# Safety_Devices.net
KiCad netlist of a schematic drawn in Altium Designer
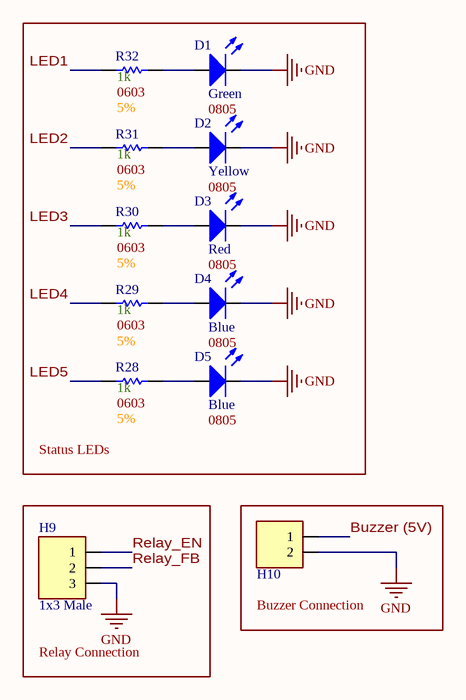
[diagram p0: Safety Devices.SchDoc]

(export (version "E")
  (design (tool "Eeschema 10.0.6"))
  (components
    (comp (ref "D1")
      (value "SMD LED")
      (footprint "[LED] SMD 0805")
      (description "Generic")
      (fields (field (name "COLOR") "Green") (field (name "SIZE PACKAGE") "0805"))
      (libsource (lib "RADM Components") (part "[LED] SMD"))
    )
    (comp (ref "D2")
      (value "SMD LED")
      (footprint "[LED] SMD 0805")
      (description "Generic")
      (fields (field (name "COLOR") "Yellow") (field (name "SIZE PACKAGE") "0805"))
      (libsource (lib "RADM Components") (part "[LED] SMD"))
    )
    (comp (ref "D3")
      (value "SMD LED")
      (footprint "[LED] SMD 0805")
      (description "Generic")
      (fields (field (name "COLOR") "Red") (field (name "SIZE PACKAGE") "0805"))
      (libsource (lib "RADM Components") (part "[LED] SMD"))
    )
    (comp (ref "D4")
      (value "SMD LED")
      (footprint "[LED] SMD 0805")
      (description "Generic")
      (fields (field (name "COLOR") "Blue") (field (name "SIZE PACKAGE") "0805"))
      (libsource (lib "RADM Components") (part "[LED] SMD"))
    )
    (comp (ref "D5")
      (value "SMD LED")
      (footprint "[LED] SMD 0805")
      (description "Generic")
      (fields (field (name "COLOR") "Blue") (field (name "SIZE PACKAGE") "0805"))
      (libsource (lib "RADM Components") (part "[LED] SMD"))
    )
    (comp (ref "H9")
      (value "1x3 Male")
      (footprint "[Header] Shrouded 1x3 Male")
      (description "070543-0037\r\nMates with 005057-9403")
      (libsource (lib "RADM Connectors") (part "[Header] Shrouded 1x3 Male"))
    )
    (comp (ref "H10")
      (value "1x2 Male")
      (footprint "[Header] Shrouded 1x2 Male")
      (description "0705430036\r\nMates with 0050579402")
      (libsource (lib "RADM Connectors") (part "[Header] Shrouded 1x2 Male"))
    )
    (comp (ref "R28")
      (value "[Res] SMD Resistor")
      (footprint "[Res] SMD 0603")
      (description "Generic")
      (fields
        (field (name "RESISTANCE") "1k")
        (field (name "SIZE PACKAGE") "0603")
        (field (name "TOLERANCE") "5%")
      )
      (libsource (lib "RADM Components") (part "[Res] SMD Resistor"))
    )
    (comp (ref "R29")
      (value "[Res] SMD Resistor")
      (footprint "[Res] SMD 0603")
      (description "Generic")
      (fields
        (field (name "RESISTANCE") "1k")
        (field (name "SIZE PACKAGE") "0603")
        (field (name "TOLERANCE") "5%")
      )
      (libsource (lib "RADM Components") (part "[Res] SMD Resistor"))
    )
    (comp (ref "R30")
      (value "[Res] SMD Resistor")
      (footprint "[Res] SMD 0603")
      (description "Generic")
      (fields
        (field (name "RESISTANCE") "1k")
        (field (name "SIZE PACKAGE") "0603")
        (field (name "TOLERANCE") "5%")
      )
      (libsource (lib "RADM Components") (part "[Res] SMD Resistor"))
    )
    (comp (ref "R31")
      (value "[Res] SMD Resistor")
      (footprint "[Res] SMD 0603")
      (description "Generic")
      (fields
        (field (name "RESISTANCE") "1k")
        (field (name "SIZE PACKAGE") "0603")
        (field (name "TOLERANCE") "5%")
      )
      (libsource (lib "RADM Components") (part "[Res] SMD Resistor"))
    )
    (comp (ref "R32")
      (value "[Res] SMD Resistor")
      (footprint "[Res] SMD 0603")
      (description "Generic")
      (fields
        (field (name "RESISTANCE") "1k")
        (field (name "SIZE PACKAGE") "0603")
        (field (name "TOLERANCE") "5%")
      )
      (libsource (lib "RADM Components") (part "[Res] SMD Resistor"))
    )
  )
  (nets
    (net (code "1") (name "/Buzzer (5V)") (class "Default")
      (node (ref "H10") (pin "1") (pinfunction "1_1") (pintype "passive"))
    )
    (net (code "2") (name "/LED1") (class "Default")
      (node (ref "R32") (pin "2") (pinfunction "2_2") (pintype "passive"))
    )
    (net (code "3") (name "/LED2") (class "Default")
      (node (ref "R31") (pin "2") (pinfunction "2_2") (pintype "passive"))
    )
    (net (code "4") (name "/LED3") (class "Default")
      (node (ref "R30") (pin "2") (pinfunction "2_2") (pintype "passive"))
    )
    (net (code "5") (name "/LED4") (class "Default")
      (node (ref "R29") (pin "2") (pinfunction "2_2") (pintype "passive"))
    )
    (net (code "6") (name "/LED5") (class "Default")
      (node (ref "R28") (pin "2") (pinfunction "2_2") (pintype "passive"))
    )
    (net (code "7") (name "/Relay_EN") (class "Default")
      (node (ref "H9") (pin "1") (pinfunction "1_1") (pintype "passive"))
    )
    (net (code "8") (name "/Relay_FB") (class "Default")
      (node (ref "H9") (pin "2") (pinfunction "2_2") (pintype "passive"))
    )
    (net (code "9") (name "GND") (class "Default")
      (node (ref "D1") (pin "2") (pinfunction "Cathode_2") (pintype "passive"))
      (node (ref "D2") (pin "2") (pinfunction "Cathode_2") (pintype "passive"))
      (node (ref "D3") (pin "2") (pinfunction "Cathode_2") (pintype "passive"))
      (node (ref "D4") (pin "2") (pinfunction "Cathode_2") (pintype "passive"))
      (node (ref "D5") (pin "2") (pinfunction "Cathode_2") (pintype "passive"))
      (node (ref "H10") (pin "2") (pinfunction "2_2") (pintype "passive"))
      (node (ref "H9") (pin "3") (pinfunction "3_3") (pintype "passive"))
    )
    (net (code "10") (name "Net-(D1-Anode)") (class "Default")
      (node (ref "D1") (pin "1") (pinfunction "Anode_1") (pintype "passive"))
      (node (ref "R32") (pin "1") (pinfunction "1_1") (pintype "passive"))
    )
    (net (code "11") (name "Net-(D2-Anode)") (class "Default")
      (node (ref "D2") (pin "1") (pinfunction "Anode_1") (pintype "passive"))
      (node (ref "R31") (pin "1") (pinfunction "1_1") (pintype "passive"))
    )
    (net (code "12") (name "Net-(D3-Anode)") (class "Default")
      (node (ref "D3") (pin "1") (pinfunction "Anode_1") (pintype "passive"))
      (node (ref "R30") (pin "1") (pinfunction "1_1") (pintype "passive"))
    )
    (net (code "13") (name "Net-(D4-Anode)") (class "Default")
      (node (ref "D4") (pin "1") (pinfunction "Anode_1") (pintype "passive"))
      (node (ref "R29") (pin "1") (pinfunction "1_1") (pintype "passive"))
    )
    (net (code "14") (name "Net-(D5-Anode)") (class "Default")
      (node (ref "D5") (pin "1") (pinfunction "Anode_1") (pintype "passive"))
      (node (ref "R28") (pin "1") (pinfunction "1_1") (pintype "passive"))
    )
  )
)
